# 2_Power.net
KiCad netlist of a schematic drawn in Altium Designer
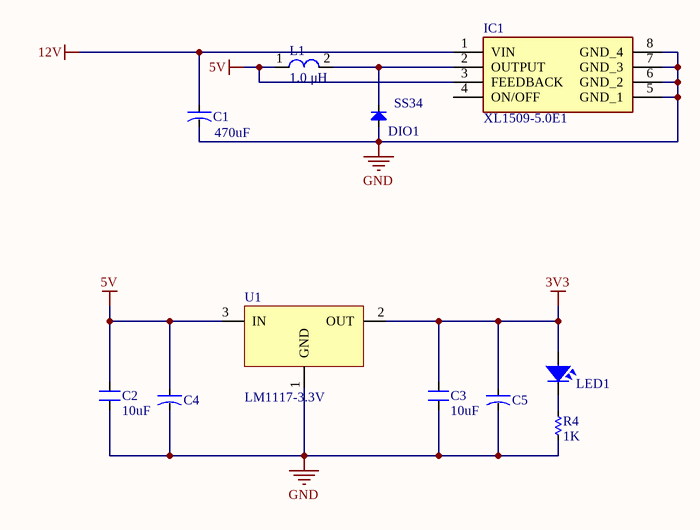
[diagram p0: [2]Power.SchDoc]

(export (version "E")
  (design (tool "Eeschema 10.0.6"))
  (components
    (comp (ref "C1")
      (value "470uF")
      (footprint "CAP-ALU-SMD-6.3x7.7x2.2")
      (description "Polarized Capacitor (Axial)")
      (fields (field (name "PUBLISHER") "Altium Limited"))
      (libsource (lib "LIBTanCN") (part "CN-ALU-SMD"))
    )
    (comp (ref "C2")
      (value "10uF")
      (footprint "CN-SMD-0603")
      (description "Tu gom")
      (libsource (lib "LIBTanCN") (part "CN"))
    )
    (comp (ref "C3")
      (value "10uF")
      (footprint "CN-SMD-0603")
      (description "Tu gom")
      (libsource (lib "LIBTanCN") (part "CN"))
    )
    (comp (ref "C4")
      (value "CN-ALU-SMD")
      (footprint "CAP-ALU-SMD-4.5x5x1.4")
      (description "Polarized Capacitor (Axial)")
      (fields (field (name "PUBLISHER") "Altium Limited"))
      (libsource (lib "LIBTanCN") (part "CN-ALU-SMD"))
    )
    (comp (ref "C5")
      (value "CN-ALU-SMD")
      (footprint "CAP-ALU-SMD-4.5x5x1.4")
      (description "Polarized Capacitor (Axial)")
      (fields (field (name "PUBLISHER") "Altium Limited"))
      (libsource (lib "LIBTanCN") (part "CN-ALU-SMD"))
    )
    (comp (ref "DIO1")
      (value "SS34")
      (footprint "DIO-SMD-106")
      (description "Default Diode")
      (fields (field (name "PUBLISHER") "Altium Limited"))
      (libsource (lib "LIBRARY") (part "Diode SMD"))
    )
    (comp (ref "IC1")
      (value "XL1509-5.0E1")
      (footprint "SamacSys:SOIC127P600X175-8N")
      (description "Integrated Circuit")
      (libsource (lib "*") (part "XL1509-5.0E1"))
    )
    (comp (ref "L1")
      (value "1.0 μH")
      (footprint "L-SMD-M-7.3x4.5")
      (fields
        (field (name "PARTNO") "78477010")
        (field (name "MANUFACTURER") "Wurth Elektronik")
        (field (name "CREATED BY") "Baojun Chen")
      )
      (libsource (lib "LIBTanCN") (part "L-SMD-1"))
    )
    (comp (ref "LED1") (value "LED") (footprint "LED-0805-Blue") (libsource (lib "LIBRARY") (part "LED SMD")))
    (comp (ref "R4")
      (value "1K")
      (footprint "RES-SMD-0603")
      (description "Resistor")
      (fields
        (field (name "MANUFACTURER") "Generic Components")
        (field (name "PUBLISHER") "Altium Hobart Technology Centre")
      )
      (libsource (lib "LIBRARY") (part "Res-SMD"))
    )
    (comp (ref "U1")
      (value "LM1117-3.3V")
      (footprint "SOT223")
      (description "800mA Low-Dropout Linear Regulator")
      (fields (field (name "CREATOR") "Nguyen Ba Bien"))
      (libsource (lib "LIBRARY") (part "LM1117"))
    )
  )
  (nets
    (net (code "1") (name "3V3") (class "Default")
      (node (ref "C3") (pin "1") (pinfunction "1_1") (pintype "passive"))
      (node (ref "C5") (pin "1") (pinfunction "1_1") (pintype "passive"))
      (node (ref "LED1") (pin "1") (pinfunction "1_1") (pintype "passive"))
      (node (ref "U1") (pin "2") (pinfunction "OUT_2") (pintype "passive"))
    )
    (net (code "2") (name "5V") (class "Default")
      (node (ref "C2") (pin "1") (pinfunction "1_1") (pintype "passive"))
      (node (ref "C4") (pin "1") (pinfunction "1_1") (pintype "passive"))
      (node (ref "IC1") (pin "3") (pinfunction "FEEDBACK_3") (pintype "passive"))
      (node (ref "L1") (pin "1") (pinfunction "1_1") (pintype "passive"))
      (node (ref "U1") (pin "3") (pinfunction "IN_3") (pintype "passive"))
    )
    (net (code "3") (name "12V") (class "Default")
      (node (ref "C1") (pin "1") (pinfunction "1_1") (pintype "passive"))
      (node (ref "IC1") (pin "1") (pinfunction "VIN_1") (pintype "passive"))
    )
    (net (code "4") (name "GND") (class "Default")
      (node (ref "C1") (pin "2") (pinfunction "2_2") (pintype "passive"))
      (node (ref "C2") (pin "2") (pinfunction "2_2") (pintype "passive"))
      (node (ref "C3") (pin "2") (pinfunction "2_2") (pintype "passive"))
      (node (ref "C4") (pin "2") (pinfunction "2_2") (pintype "passive"))
      (node (ref "C5") (pin "2") (pinfunction "2_2") (pintype "passive"))
      (node (ref "DIO1") (pin "1") (pinfunction "A_1") (pintype "passive"))
      (node (ref "IC1") (pin "5") (pinfunction "GND_1_5") (pintype "passive"))
      (node (ref "IC1") (pin "6") (pinfunction "GND_2_6") (pintype "passive"))
      (node (ref "IC1") (pin "7") (pinfunction "GND_3_7") (pintype "passive"))
      (node (ref "IC1") (pin "8") (pinfunction "GND_4_8") (pintype "passive"))
      (node (ref "R4") (pin "2") (pinfunction "2_2") (pintype "passive"))
      (node (ref "U1") (pin "1") (pinfunction "GND_1") (pintype "passive"))
    )
    (net (code "5") (name "Net-(DIO1-K)") (class "Default")
      (node (ref "DIO1") (pin "2") (pinfunction "K_2") (pintype "passive"))
      (node (ref "IC1") (pin "2") (pinfunction "OUTPUT_2") (pintype "passive"))
      (node (ref "L1") (pin "2") (pinfunction "2_2") (pintype "passive"))
    )
    (net (code "6") (name "Net-(LED1-Pad2)") (class "Default")
      (node (ref "LED1") (pin "2") (pinfunction "2_2") (pintype "passive"))
      (node (ref "R4") (pin "1") (pinfunction "1_1") (pintype "passive"))
    )
    (net (code "7") (name "unconnected-(IC1-ON{slash}OFF-Pad4)") (class "Default")
      (node (ref "IC1") (pin "4") (pinfunction "ON/OFF_4") (pintype "passive"))
    )
  )
)
